# DB25-relay-HV-control.net
KiCad netlist of a schematic drawn in Altium Designer
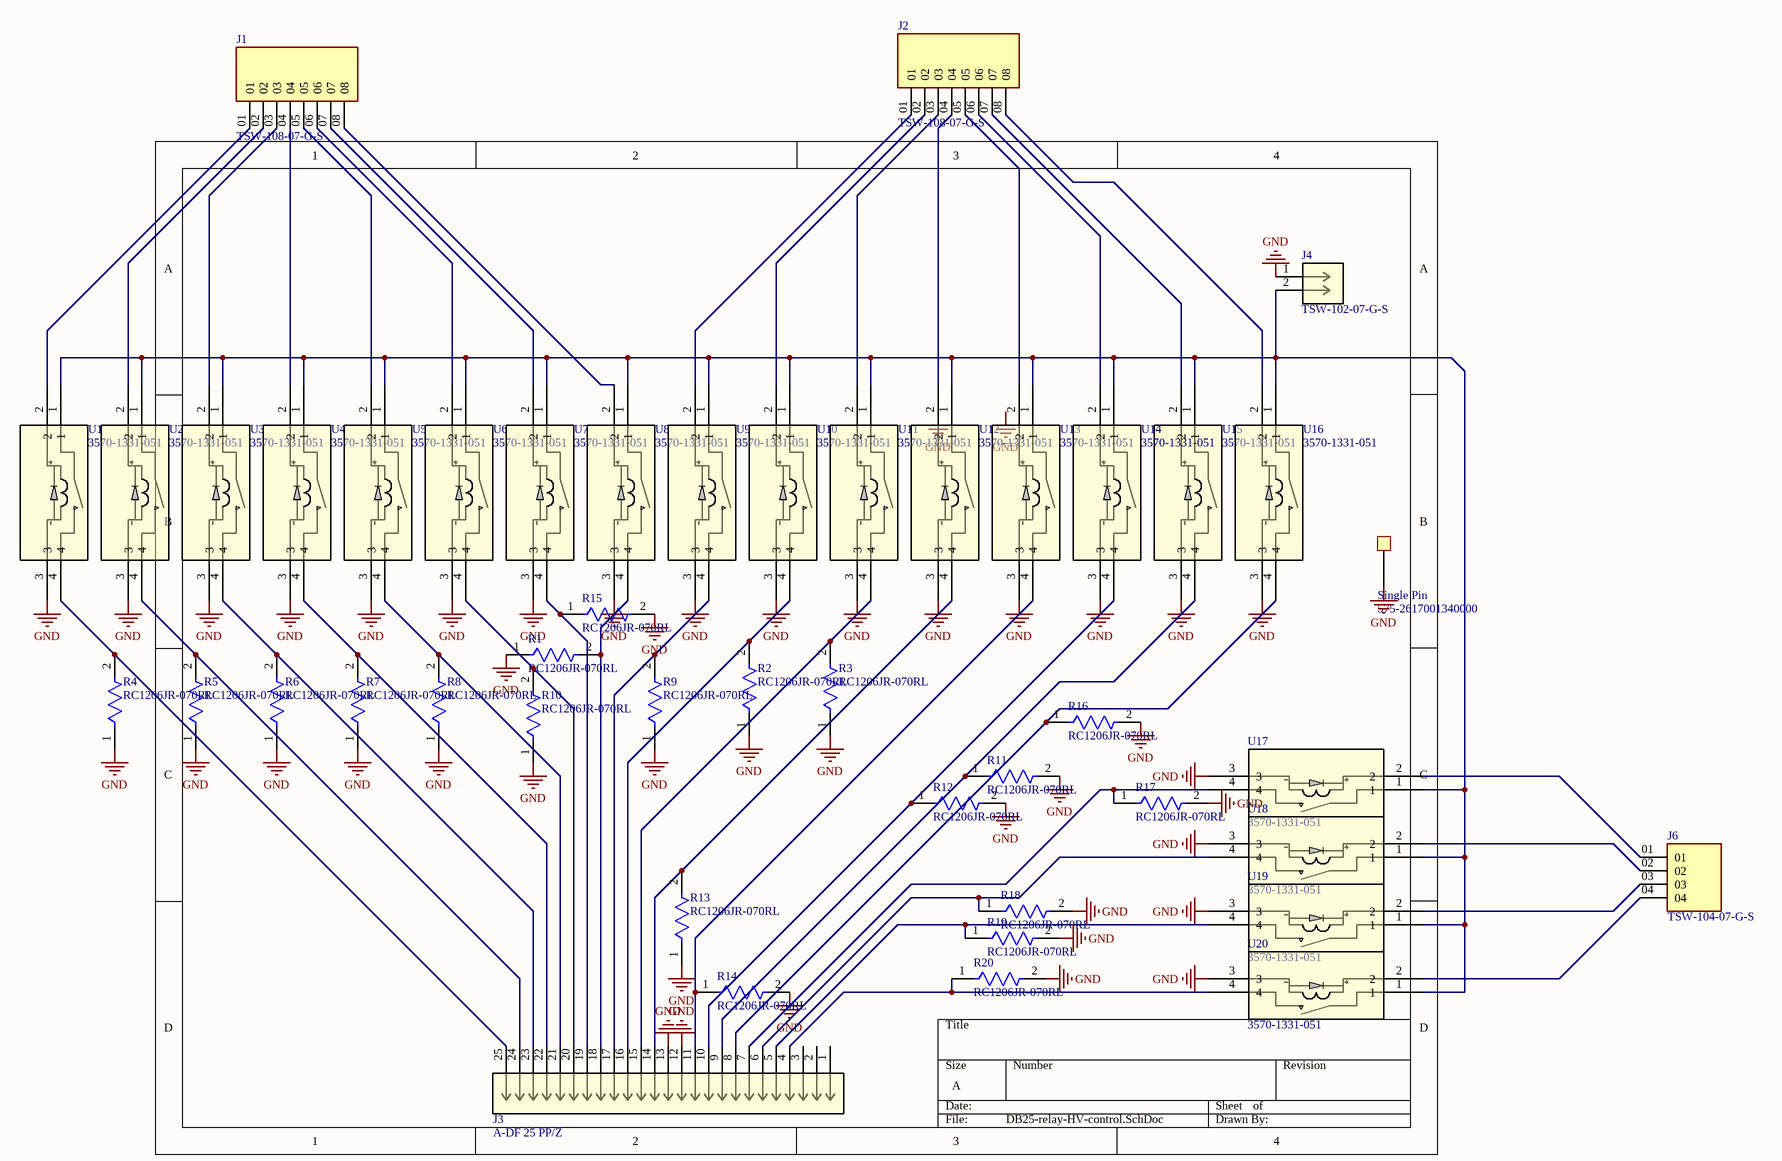
[diagram p0: DB25-relay-HV-control.SchDoc]

(export (version "E")
  (design (tool "Eeschema 10.0.6"))
  (components
    (comp (ref "J1")
      (value "TSW-108-07-G-S")
      (footprint "SAMTEC_TSW-108-07-G-S")
      (description "TSW - Samtec 2.54mm Pin Header 10.92mm Overall Pin Length (07) - Fast Stock")
      (fields (field (name "MF") "Samtec Inc."))
      (libsource (lib "SchlibLafe") (part "TSW-108-07-G-S"))
    )
    (comp (ref "J2")
      (value "TSW-108-07-G-S")
      (footprint "SAMTEC_TSW-108-07-G-S")
      (description "TSW - Samtec 2.54mm Pin Header 10.92mm Overall Pin Length (07) - Fast Stock")
      (fields (field (name "MF") "Samtec Inc."))
      (libsource (lib "SchlibLafe") (part "TSW-108-07-G-S"))
    )
    (comp (ref "J3")
      (value "A-DF 25 PP/Z")
      (footprint "CONN_A-DF 25 PPZ_ASM")
      (description "No Description Available")
      (fields (field (name "COPYRIGHT") "Copyright (C) 2024 Ultra Librarian. All rights reserved."))
      (libsource (lib "SchlibLafe") (part "A-DF 25 PPZ"))
    )
    (comp (ref "J4")
      (value "TSW-102-07-G-S")
      (footprint "CON2_1X2_TU_TSW")
      (description "No Description Available")
      (fields (field (name "COPYRIGHT") "Copyright (C) 2024 Ultra Librarian. All rights reserved."))
      (libsource (lib "SchlibLafe") (part "TSW-102-07-G-S"))
    )
    (comp (ref "J5")
      (value "Single Pin")
      (footprint "Single PC Pin")
      (fields (field (name "SUPPLIER PART NUMBER 1") "575-2617001340000"))
      (libsource (lib "SchlibLafe") (part "Single PC Pin"))
    )
    (comp (ref "J6")
      (value "TSW-104-07-G-S")
      (footprint "SAMTEC_TSW-104-07-G-S")
      (fields (field (name "MP") "altium_native_batch"))
      (libsource (lib "SchlibLafe") (part "TSW-104-07-G-S"))
    )
    (comp (ref "R1")
      (value "RC1206JR-070RL")
      (footprint "FP-RC1206-MFG")
      (description "RES SMD 0 OHM JUMPER 1/4W 1206")
      (fields
        (field (name "MANUFACTURER") "YAGEO")
        (field (name "OCTOPART") "https://octopart.com/rc1206jr-070rl-yageo-40025601")
      )
      (libsource (lib "Altium Content Vault") (part "1029c3af85768c4190bb7ad29bc67b5"))
    )
    (comp (ref "R2")
      (value "RC1206JR-070RL")
      (footprint "FP-RC1206-MFG")
      (description "RES SMD 0 OHM JUMPER 1/4W 1206")
      (fields
        (field (name "MANUFACTURER") "YAGEO")
        (field (name "OCTOPART") "https://octopart.com/rc1206jr-070rl-yageo-40025601")
      )
      (libsource (lib "Altium Content Vault") (part "1029c3af85768c4190bb7ad29bc67b5"))
    )
    (comp (ref "R3")
      (value "RC1206JR-070RL")
      (footprint "FP-RC1206-MFG")
      (description "RES SMD 0 OHM JUMPER 1/4W 1206")
      (fields
        (field (name "MANUFACTURER") "YAGEO")
        (field (name "OCTOPART") "https://octopart.com/rc1206jr-070rl-yageo-40025601")
      )
      (libsource (lib "Altium Content Vault") (part "1029c3af85768c4190bb7ad29bc67b5"))
    )
    (comp (ref "R4")
      (value "RC1206JR-070RL")
      (footprint "FP-RC1206-MFG")
      (description "RES SMD 0 OHM JUMPER 1/4W 1206")
      (fields
        (field (name "MANUFACTURER") "YAGEO")
        (field (name "OCTOPART") "https://octopart.com/rc1206jr-070rl-yageo-40025601")
      )
      (libsource (lib "Altium Content Vault") (part "1029c3af85768c4190bb7ad29bc67b5"))
    )
    (comp (ref "R5")
      (value "RC1206JR-070RL")
      (footprint "FP-RC1206-MFG")
      (description "RES SMD 0 OHM JUMPER 1/4W 1206")
      (fields
        (field (name "MANUFACTURER") "YAGEO")
        (field (name "OCTOPART") "https://octopart.com/rc1206jr-070rl-yageo-40025601")
      )
      (libsource (lib "Altium Content Vault") (part "1029c3af85768c4190bb7ad29bc67b5"))
    )
    (comp (ref "R6")
      (value "RC1206JR-070RL")
      (footprint "FP-RC1206-MFG")
      (description "RES SMD 0 OHM JUMPER 1/4W 1206")
      (fields
        (field (name "MANUFACTURER") "YAGEO")
        (field (name "OCTOPART") "https://octopart.com/rc1206jr-070rl-yageo-40025601")
      )
      (libsource (lib "Altium Content Vault") (part "1029c3af85768c4190bb7ad29bc67b5"))
    )
    (comp (ref "R7")
      (value "RC1206JR-070RL")
      (footprint "FP-RC1206-MFG")
      (description "RES SMD 0 OHM JUMPER 1/4W 1206")
      (fields
        (field (name "MANUFACTURER") "YAGEO")
        (field (name "OCTOPART") "https://octopart.com/rc1206jr-070rl-yageo-40025601")
      )
      (libsource (lib "Altium Content Vault") (part "1029c3af85768c4190bb7ad29bc67b5"))
    )
    (comp (ref "R8")
      (value "RC1206JR-070RL")
      (footprint "FP-RC1206-MFG")
      (description "RES SMD 0 OHM JUMPER 1/4W 1206")
      (fields
        (field (name "MANUFACTURER") "YAGEO")
        (field (name "OCTOPART") "https://octopart.com/rc1206jr-070rl-yageo-40025601")
      )
      (libsource (lib "Altium Content Vault") (part "1029c3af85768c4190bb7ad29bc67b5"))
    )
    (comp (ref "R9")
      (value "RC1206JR-070RL")
      (footprint "FP-RC1206-MFG")
      (description "RES SMD 0 OHM JUMPER 1/4W 1206")
      (fields
        (field (name "MANUFACTURER") "YAGEO")
        (field (name "OCTOPART") "https://octopart.com/rc1206jr-070rl-yageo-40025601")
      )
      (libsource (lib "Altium Content Vault") (part "1029c3af85768c4190bb7ad29bc67b5"))
    )
    (comp (ref "R10")
      (value "RC1206JR-070RL")
      (footprint "FP-RC1206-MFG")
      (description "RES SMD 0 OHM JUMPER 1/4W 1206")
      (fields
        (field (name "MANUFACTURER") "YAGEO")
        (field (name "OCTOPART") "https://octopart.com/rc1206jr-070rl-yageo-40025601")
      )
      (libsource (lib "Altium Content Vault") (part "1029c3af85768c4190bb7ad29bc67b5"))
    )
    (comp (ref "R11")
      (value "RC1206JR-070RL")
      (footprint "FP-RC1206-MFG")
      (description "RES SMD 0 OHM JUMPER 1/4W 1206")
      (fields
        (field (name "MANUFACTURER") "YAGEO")
        (field (name "OCTOPART") "https://octopart.com/rc1206jr-070rl-yageo-40025601")
      )
      (libsource (lib "Altium Content Vault") (part "1029c3af85768c4190bb7ad29bc67b5"))
    )
    (comp (ref "R12")
      (value "RC1206JR-070RL")
      (footprint "FP-RC1206-MFG")
      (description "RES SMD 0 OHM JUMPER 1/4W 1206")
      (fields
        (field (name "MANUFACTURER") "YAGEO")
        (field (name "OCTOPART") "https://octopart.com/rc1206jr-070rl-yageo-40025601")
      )
      (libsource (lib "Altium Content Vault") (part "1029c3af85768c4190bb7ad29bc67b5"))
    )
    (comp (ref "R13")
      (value "RC1206JR-070RL")
      (footprint "FP-RC1206-MFG")
      (description "RES SMD 0 OHM JUMPER 1/4W 1206")
      (fields
        (field (name "MANUFACTURER") "YAGEO")
        (field (name "OCTOPART") "https://octopart.com/rc1206jr-070rl-yageo-40025601")
      )
      (libsource (lib "Altium Content Vault") (part "1029c3af85768c4190bb7ad29bc67b5"))
    )
    (comp (ref "R14")
      (value "RC1206JR-070RL")
      (footprint "FP-RC1206-MFG")
      (description "RES SMD 0 OHM JUMPER 1/4W 1206")
      (fields
        (field (name "MANUFACTURER") "YAGEO")
        (field (name "OCTOPART") "https://octopart.com/rc1206jr-070rl-yageo-40025601")
      )
      (libsource (lib "Altium Content Vault") (part "1029c3af85768c4190bb7ad29bc67b5"))
    )
    (comp (ref "R15")
      (value "RC1206JR-070RL")
      (footprint "FP-RC1206-MFG")
      (description "RES SMD 0 OHM JUMPER 1/4W 1206")
      (fields
        (field (name "MANUFACTURER") "YAGEO")
        (field (name "OCTOPART") "https://octopart.com/rc1206jr-070rl-yageo-40025601")
      )
      (libsource (lib "Altium Content Vault") (part "1029c3af85768c4190bb7ad29bc67b5"))
    )
    (comp (ref "R16")
      (value "RC1206JR-070RL")
      (footprint "FP-RC1206-MFG")
      (description "RES SMD 0 OHM JUMPER 1/4W 1206")
      (fields
        (field (name "MANUFACTURER") "YAGEO")
        (field (name "OCTOPART") "https://octopart.com/rc1206jr-070rl-yageo-40025601")
      )
      (libsource (lib "Altium Content Vault") (part "1029c3af85768c4190bb7ad29bc67b5"))
    )
    (comp (ref "R17")
      (value "RC1206JR-070RL")
      (footprint "FP-RC1206-MFG")
      (description "RES SMD 0 OHM JUMPER 1/4W 1206")
      (fields
        (field (name "MANUFACTURER") "YAGEO")
        (field (name "OCTOPART") "https://octopart.com/rc1206jr-070rl-yageo-40025601")
      )
      (libsource (lib "Altium Content Vault") (part "1029c3af85768c4190bb7ad29bc67b5"))
    )
    (comp (ref "R18")
      (value "RC1206JR-070RL")
      (footprint "FP-RC1206-MFG")
      (description "RES SMD 0 OHM JUMPER 1/4W 1206")
      (fields
        (field (name "MANUFACTURER") "YAGEO")
        (field (name "OCTOPART") "https://octopart.com/rc1206jr-070rl-yageo-40025601")
      )
      (libsource (lib "Altium Content Vault") (part "1029c3af85768c4190bb7ad29bc67b5"))
    )
    (comp (ref "R19")
      (value "RC1206JR-070RL")
      (footprint "FP-RC1206-MFG")
      (description "RES SMD 0 OHM JUMPER 1/4W 1206")
      (fields
        (field (name "MANUFACTURER") "YAGEO")
        (field (name "OCTOPART") "https://octopart.com/rc1206jr-070rl-yageo-40025601")
      )
      (libsource (lib "Altium Content Vault") (part "1029c3af85768c4190bb7ad29bc67b5"))
    )
    (comp (ref "R20")
      (value "RC1206JR-070RL")
      (footprint "FP-RC1206-MFG")
      (description "RES SMD 0 OHM JUMPER 1/4W 1206")
      (fields
        (field (name "MANUFACTURER") "YAGEO")
        (field (name "OCTOPART") "https://octopart.com/rc1206jr-070rl-yageo-40025601")
      )
      (libsource (lib "Altium Content Vault") (part "1029c3af85768c4190bb7ad29bc67b5"))
    )
    (comp (ref "U1")
      (value "3570-1331-051")
      (footprint "SIP_3570-1331_COM")
      (description "No Description Available")
      (fields (field (name "COPYRIGHT") "Copyright (C) 2024 Ultra Librarian. All rights reserved."))
      (libsource (lib "") (part "3570-1331-051_2"))
    )
    (comp (ref "U2")
      (value "3570-1331-051")
      (footprint "SIP_3570-1331_COM")
      (description "No Description Available")
      (fields (field (name "COPYRIGHT") "Copyright (C) 2024 Ultra Librarian. All rights reserved."))
      (libsource (lib "") (part "3570-1331-051_3"))
    )
    (comp (ref "U3")
      (value "3570-1331-051")
      (footprint "SIP_3570-1331_COM")
      (description "No Description Available")
      (fields (field (name "COPYRIGHT") "Copyright (C) 2024 Ultra Librarian. All rights reserved."))
      (libsource (lib "SchlibAnna") (part "3570-1331-051"))
    )
    (comp (ref "U4")
      (value "3570-1331-051")
      (footprint "SIP_3570-1331_COM")
      (description "No Description Available")
      (fields (field (name "COPYRIGHT") "Copyright (C) 2024 Ultra Librarian. All rights reserved."))
      (libsource (lib "SchlibAnna") (part "3570-1331-051"))
    )
    (comp (ref "U5")
      (value "3570-1331-051")
      (footprint "SIP_3570-1331_COM")
      (description "No Description Available")
      (fields (field (name "COPYRIGHT") "Copyright (C) 2024 Ultra Librarian. All rights reserved."))
      (libsource (lib "SchlibAnna") (part "3570-1331-051"))
    )
    (comp (ref "U6")
      (value "3570-1331-051")
      (footprint "SIP_3570-1331_COM")
      (description "No Description Available")
      (fields (field (name "COPYRIGHT") "Copyright (C) 2024 Ultra Librarian. All rights reserved."))
      (libsource (lib "SchlibAnna") (part "3570-1331-051"))
    )
    (comp (ref "U7")
      (value "3570-1331-051")
      (footprint "SIP_3570-1331_COM")
      (description "No Description Available")
      (fields (field (name "COPYRIGHT") "Copyright (C) 2024 Ultra Librarian. All rights reserved."))
      (libsource (lib "SchlibAnna") (part "3570-1331-051"))
    )
    (comp (ref "U8")
      (value "3570-1331-051")
      (footprint "SIP_3570-1331_COM")
      (description "No Description Available")
      (fields (field (name "COPYRIGHT") "Copyright (C) 2024 Ultra Librarian. All rights reserved."))
      (libsource (lib "SchlibAnna") (part "3570-1331-051"))
    )
    (comp (ref "U9")
      (value "3570-1331-051")
      (footprint "SIP_3570-1331_COM")
      (description "No Description Available")
      (fields (field (name "COPYRIGHT") "Copyright (C) 2024 Ultra Librarian. All rights reserved."))
      (libsource (lib "SchlibAnna") (part "3570-1331-051"))
    )
    (comp (ref "U10")
      (value "3570-1331-051")
      (footprint "SIP_3570-1331_COM")
      (description "No Description Available")
      (fields (field (name "COPYRIGHT") "Copyright (C) 2024 Ultra Librarian. All rights reserved."))
      (libsource (lib "SchlibAnna") (part "3570-1331-051"))
    )
    (comp (ref "U11")
      (value "3570-1331-051")
      (footprint "SIP_3570-1331_COM")
      (description "No Description Available")
      (fields (field (name "COPYRIGHT") "Copyright (C) 2024 Ultra Librarian. All rights reserved."))
      (libsource (lib "SchlibAnna") (part "3570-1331-051"))
    )
    (comp (ref "U12")
      (value "3570-1331-051")
      (footprint "SIP_3570-1331_COM")
      (description "No Description Available")
      (fields (field (name "COPYRIGHT") "Copyright (C) 2024 Ultra Librarian. All rights reserved."))
      (libsource (lib "SchlibAnna") (part "3570-1331-051"))
    )
    (comp (ref "U13")
      (value "3570-1331-051")
      (footprint "SIP_3570-1331_COM")
      (description "No Description Available")
      (fields (field (name "COPYRIGHT") "Copyright (C) 2024 Ultra Librarian. All rights reserved."))
      (libsource (lib "SchlibAnna") (part "3570-1331-051"))
    )
    (comp (ref "U14")
      (value "3570-1331-051")
      (footprint "SIP_3570-1331_COM")
      (description "No Description Available")
      (fields (field (name "COPYRIGHT") "Copyright (C) 2024 Ultra Librarian. All rights reserved."))
      (libsource (lib "SchlibAnna") (part "3570-1331-051"))
    )
    (comp (ref "U15")
      (value "3570-1331-051")
      (footprint "SIP_3570-1331_COM")
      (description "No Description Available")
      (fields (field (name "COPYRIGHT") "Copyright (C) 2024 Ultra Librarian. All rights reserved."))
      (libsource (lib "SchlibAnna") (part "3570-1331-051"))
    )
    (comp (ref "U16")
      (value "3570-1331-051")
      (footprint "SIP_3570-1331_COM")
      (description "No Description Available")
      (fields (field (name "COPYRIGHT") "Copyright (C) 2024 Ultra Librarian. All rights reserved."))
      (libsource (lib "SchlibAnna") (part "3570-1331-051"))
    )
    (comp (ref "U17")
      (value "3570-1331-051")
      (footprint "SIP_3570-1331_COM")
      (description "No Description Available")
      (fields (field (name "COPYRIGHT") "Copyright (C) 2024 Ultra Librarian. All rights reserved."))
      (libsource (lib "") (part "3570-1331-051_1"))
    )
    (comp (ref "U18")
      (value "3570-1331-051")
      (footprint "SIP_3570-1331_COM")
      (description "No Description Available")
      (fields (field (name "COPYRIGHT") "Copyright (C) 2024 Ultra Librarian. All rights reserved."))
      (libsource (lib "") (part "3570-1331-051_1"))
    )
    (comp (ref "U19")
      (value "3570-1331-051")
      (footprint "SIP_3570-1331_COM")
      (description "No Description Available")
      (fields (field (name "COPYRIGHT") "Copyright (C) 2024 Ultra Librarian. All rights reserved."))
      (libsource (lib "") (part "3570-1331-051_1"))
    )
    (comp (ref "U20")
      (value "3570-1331-051")
      (footprint "SIP_3570-1331_COM")
      (description "No Description Available")
      (fields (field (name "COPYRIGHT") "Copyright (C) 2024 Ultra Librarian. All rights reserved."))
      (libsource (lib "") (part "3570-1331-051_1"))
    )
  )
  (nets
    (net (code "1") (name "GND") (class "Default")
      (node (ref "J3") (pin "12") (pinfunction "12_12") (pintype "passive"))
      (node (ref "J3") (pin "13") (pinfunction "13_13") (pintype "passive"))
      (node (ref "J4") (pin "1") (pinfunction "1_1") (pintype "passive"))
      (node (ref "J5") (pin "1") (pinfunction "1_1") (pintype "passive"))
      (node (ref "R1") (pin "1") (pinfunction "1_1") (pintype "passive"))
      (node (ref "R10") (pin "1") (pinfunction "1_1") (pintype "passive"))
      (node (ref "R11") (pin "2") (pinfunction "2_2") (pintype "passive"))
      (node (ref "R12") (pin "2") (pinfunction "2_2") (pintype "passive"))
      (node (ref "R13") (pin "1") (pinfunction "1_1") (pintype "passive"))
      (node (ref "R14") (pin "2") (pinfunction "2_2") (pintype "passive"))
      (node (ref "R15") (pin "2") (pinfunction "2_2") (pintype "passive"))
      (node (ref "R16") (pin "2") (pinfunction "2_2") (pintype "passive"))
      (node (ref "R17") (pin "2") (pinfunction "2_2") (pintype "passive"))
      (node (ref "R18") (pin "2") (pinfunction "2_2") (pintype "passive"))
      (node (ref "R19") (pin "2") (pinfunction "2_2") (pintype "passive"))
      (node (ref "R2") (pin "1") (pinfunction "1_1") (pintype "passive"))
      (node (ref "R20") (pin "2") (pinfunction "2_2") (pintype "passive"))
      (node (ref "R3") (pin "1") (pinfunction "1_1") (pintype "passive"))
      (node (ref "R4") (pin "1") (pinfunction "1_1") (pintype "passive"))
      (node (ref "R5") (pin "1") (pinfunction "1_1") (pintype "passive"))
      (node (ref "R6") (pin "1") (pinfunction "1_1") (pintype "passive"))
      (node (ref "R7") (pin "1") (pinfunction "1_1") (pintype "passive"))
      (node (ref "R8") (pin "1") (pinfunction "1_1") (pintype "passive"))
      (node (ref "R9") (pin "1") (pinfunction "1_1") (pintype "passive"))
      (node (ref "U1") (pin "3") (pinfunction "3_3") (pintype "passive"))
      (node (ref "U10") (pin "3") (pinfunction "3_3") (pintype "passive"))
      (node (ref "U11") (pin "3") (pinfunction "3_3") (pintype "passive"))
      (node (ref "U12") (pin "3") (pinfunction "3_3") (pintype "passive"))
      (node (ref "U13") (pin "3") (pinfunction "3_3") (pintype "passive"))
      (node (ref "U14") (pin "3") (pinfunction "3_3") (pintype "passive"))
      (node (ref "U15") (pin "3") (pinfunction "3_3") (pintype "passive"))
      (node (ref "U16") (pin "3") (pinfunction "3_3") (pintype "passive"))
      (node (ref "U17") (pin "3") (pinfunction "3_3") (pintype "passive"))
      (node (ref "U18") (pin "3") (pinfunction "3_3") (pintype "passive"))
      (node (ref "U19") (pin "3") (pinfunction "3_3") (pintype "passive"))
      (node (ref "U2") (pin "3") (pinfunction "3_3") (pintype "passive"))
      (node (ref "U20") (pin "3") (pinfunction "3_3") (pintype "passive"))
      (node (ref "U3") (pin "3") (pinfunction "3_3") (pintype "passive"))
      (node (ref "U4") (pin "3") (pinfunction "3_3") (pintype "passive"))
      (node (ref "U5") (pin "3") (pinfunction "3_3") (pintype "passive"))
      (node (ref "U6") (pin "3") (pinfunction "3_3") (pintype "passive"))
      (node (ref "U7") (pin "3") (pinfunction "3_3") (pintype "passive"))
      (node (ref "U8") (pin "3") (pinfunction "3_3") (pintype "passive"))
      (node (ref "U9") (pin "3") (pinfunction "3_3") (pintype "passive"))
    )
    (net (code "2") (name "Net-(J1-Pad01)") (class "Default")
      (node (ref "J1") (pin "01") (pinfunction "01_01") (pintype "passive"))
      (node (ref "U1") (pin "2") (pinfunction "2_2") (pintype "passive"))
    )
    (net (code "3") (name "Net-(J1-Pad02)") (class "Default")
      (node (ref "J1") (pin "02") (pinfunction "02_02") (pintype "passive"))
      (node (ref "U2") (pin "2") (pinfunction "2_2") (pintype "passive"))
    )
    (net (code "4") (name "Net-(J1-Pad03)") (class "Default")
      (node (ref "J1") (pin "03") (pinfunction "03_03") (pintype "passive"))
      (node (ref "U3") (pin "2") (pinfunction "2_2") (pintype "passive"))
    )
    (net (code "5") (name "Net-(J1-Pad04)") (class "Default")
      (node (ref "J1") (pin "04") (pinfunction "04_04") (pintype "passive"))
      (node (ref "U4") (pin "2") (pinfunction "2_2") (pintype "passive"))
    )
    (net (code "6") (name "Net-(J1-Pad05)") (class "Default")
      (node (ref "J1") (pin "05") (pinfunction "05_05") (pintype "passive"))
      (node (ref "U5") (pin "2") (pinfunction "2_2") (pintype "passive"))
    )
    (net (code "7") (name "Net-(J1-Pad06)") (class "Default")
      (node (ref "J1") (pin "06") (pinfunction "06_06") (pintype "passive"))
      (node (ref "U6") (pin "2") (pinfunction "2_2") (pintype "passive"))
    )
    (net (code "8") (name "Net-(J1-Pad07)") (class "Default")
      (node (ref "J1") (pin "07") (pinfunction "07_07") (pintype "passive"))
      (node (ref "U7") (pin "2") (pinfunction "2_2") (pintype "passive"))
    )
    (net (code "9") (name "Net-(J1-Pad08)") (class "Default")
      (node (ref "J1") (pin "08") (pinfunction "08_08") (pintype "passive"))
      (node (ref "U8") (pin "2") (pinfunction "2_2") (pintype "passive"))
    )
    (net (code "10") (name "Net-(J2-Pad01)") (class "Default")
      (node (ref "J2") (pin "01") (pinfunction "01_01") (pintype "passive"))
      (node (ref "U9") (pin "2") (pinfunction "2_2") (pintype "passive"))
    )
    (net (code "11") (name "Net-(J2-Pad02)") (class "Default")
      (node (ref "J2") (pin "02") (pinfunction "02_02") (pintype "passive"))
      (node (ref "U10") (pin "2") (pinfunction "2_2") (pintype "passive"))
    )
    (net (code "12") (name "Net-(J2-Pad03)") (class "Default")
      (node (ref "J2") (pin "03") (pinfunction "03_03") (pintype "passive"))
      (node (ref "U11") (pin "2") (pinfunction "2_2") (pintype "passive"))
    )
    (net (code "13") (name "Net-(J2-Pad04)") (class "Default")
      (node (ref "J2") (pin "04") (pinfunction "04_04") (pintype "passive"))
      (node (ref "U12") (pin "2") (pinfunction "2_2") (pintype "passive"))
    )
    (net (code "14") (name "Net-(J2-Pad05)") (class "Default")
      (node (ref "J2") (pin "05") (pinfunction "05_05") (pintype "passive"))
      (node (ref "U13") (pin "2") (pinfunction "2_2") (pintype "passive"))
    )
    (net (code "15") (name "Net-(J2-Pad06)") (class "Default")
      (node (ref "J2") (pin "06") (pinfunction "06_06") (pintype "passive"))
      (node (ref "U14") (pin "2") (pinfunction "2_2") (pintype "passive"))
    )
    (net (code "16") (name "Net-(J2-Pad07)") (class "Default")
      (node (ref "J2") (pin "07") (pinfunction "07_07") (pintype "passive"))
      (node (ref "U15") (pin "2") (pinfunction "2_2") (pintype "passive"))
    )
    (net (code "17") (name "Net-(J2-Pad08)") (class "Default")
      (node (ref "J2") (pin "08") (pinfunction "08_08") (pintype "passive"))
      (node (ref "U16") (pin "2") (pinfunction "2_2") (pintype "passive"))
    )
    (net (code "18") (name "Net-(J3-Pad4)") (class "Default")
      (node (ref "J3") (pin "4") (pinfunction "4_4") (pintype "passive"))
      (node (ref "R20") (pin "1") (pinfunction "1_1") (pintype "passive"))
      (node (ref "U20") (pin "4") (pinfunction "4_4") (pintype "passive"))
    )
    (net (code "19") (name "Net-(J3-Pad5)") (class "Default")
      (node (ref "J3") (pin "5") (pinfunction "5_5") (pintype "passive"))
      (node (ref "R19") (pin "1") (pinfunction "1_1") (pintype "passive"))
      (node (ref "U19") (pin "4") (pinfunction "4_4") (pintype "passive"))
    )
    (net (code "20") (name "Net-(J3-Pad6)") (class "Default")
      (node (ref "J3") (pin "6") (pinfunction "6_6") (pintype "passive"))
      (node (ref "R18") (pin "1") (pinfunction "1_1") (pintype "passive"))
      (node (ref "U18") (pin "4") (pinfunction "4_4") (pintype "passive"))
    )
    (net (code "21") (name "Net-(J3-Pad7)") (class "Default")
      (node (ref "J3") (pin "7") (pinfunction "7_7") (pintype "passive"))
      (node (ref "R17") (pin "1") (pinfunction "1_1") (pintype "passive"))
      (node (ref "U17") (pin "4") (pinfunction "4_4") (pintype "passive"))
    )
    (net (code "22") (name "Net-(J3-Pad8)") (class "Default")
      (node (ref "J3") (pin "8") (pinfunction "8_8") (pintype "passive"))
      (node (ref "R16") (pin "1") (pinfunction "1_1") (pintype "passive"))
      (node (ref "U16") (pin "4") (pinfunction "4_4") (pintype "passive"))
    )
    (net (code "23") (name "Net-(J3-Pad9)") (class "Default")
      (node (ref "J3") (pin "9") (pinfunction "9_9") (pintype "passive"))
      (node (ref "R11") (pin "1") (pinfunction "1_1") (pintype "passive"))
      (node (ref "U15") (pin "4") (pinfunction "4_4") (pintype "passive"))
    )
    (net (code "24") (name "Net-(J3-Pad10)") (class "Default")
      (node (ref "J3") (pin "10") (pinfunction "10_10") (pintype "passive"))
      (node (ref "R12") (pin "1") (pinfunction "1_1") (pintype "passive"))
      (node (ref "U14") (pin "4") (pinfunction "4_4") (pintype "passive"))
    )
    (net (code "25") (name "Net-(J3-Pad11)") (class "Default")
      (node (ref "J3") (pin "11") (pinfunction "11_11") (pintype "passive"))
      (node (ref "R14") (pin "1") (pinfunction "1_1") (pintype "passive"))
      (node (ref "U13") (pin "4") (pinfunction "4_4") (pintype "passive"))
    )
    (net (code "26") (name "Net-(J3-Pad14)") (class "Default")
      (node (ref "J3") (pin "14") (pinfunction "14_14") (pintype "passive"))
      (node (ref "R13") (pin "2") (pinfunction "2_2") (pintype "passive"))
      (node (ref "U12") (pin "4") (pinfunction "4_4") (pintype "passive"))
    )
    (net (code "27") (name "Net-(J3-Pad15)") (class "Default")
      (node (ref "J3") (pin "15") (pinfunction "15_15") (pintype "passive"))
      (node (ref "R3") (pin "2") (pinfunction "2_2") (pintype "passive"))
      (node (ref "U11") (pin "4") (pinfunction "4_4") (pintype "passive"))
    )
    (net (code "28") (name "Net-(J3-Pad16)") (class "Default")
      (node (ref "J3") (pin "16") (pinfunction "16_16") (pintype "passive"))
      (node (ref "R2") (pin "2") (pinfunction "2_2") (pintype "passive"))
      (node (ref "U10") (pin "4") (pinfunction "4_4") (pintype "passive"))
    )
    (net (code "29") (name "Net-(J3-Pad17)") (class "Default")
      (node (ref "J3") (pin "17") (pinfunction "17_17") (pintype "passive"))
      (node (ref "R9") (pin "2") (pinfunction "2_2") (pintype "passive"))
      (node (ref "U9") (pin "4") (pinfunction "4_4") (pintype "passive"))
    )
    (net (code "30") (name "Net-(J3-Pad18)") (class "Default")
      (node (ref "J3") (pin "18") (pinfunction "18_18") (pintype "passive"))
      (node (ref "R1") (pin "2") (pinfunction "2_2") (pintype "passive"))
      (node (ref "U8") (pin "4") (pinfunction "4_4") (pintype "passive"))
    )
    (net (code "31") (name "Net-(J3-Pad19)") (class "Default")
      (node (ref "J3") (pin "19") (pinfunction "19_19") (pintype "passive"))
      (node (ref "R15") (pin "1") (pinfunction "1_1") (pintype "passive"))
      (node (ref "U7") (pin "4") (pinfunction "4_4") (pintype "passive"))
    )
    (net (code "32") (name "Net-(J3-Pad20)") (class "Default")
      (node (ref "J3") (pin "20") (pinfunction "20_20") (pintype "passive"))
      (node (ref "R10") (pin "2") (pinfunction "2_2") (pintype "passive"))
      (node (ref "U6") (pin "4") (pinfunction "4_4") (pintype "passive"))
    )
    (net (code "33") (name "Net-(J3-Pad21)") (class "Default")
      (node (ref "J3") (pin "21") (pinfunction "21_21") (pintype "passive"))
      (node (ref "R8") (pin "2") (pinfunction "2_2") (pintype "passive"))
      (node (ref "U5") (pin "4") (pinfunction "4_4") (pintype "passive"))
    )
    (net (code "34") (name "Net-(J3-Pad22)") (class "Default")
      (node (ref "J3") (pin "22") (pinfunction "22_22") (pintype "passive"))
      (node (ref "R7") (pin "2") (pinfunction "2_2") (pintype "passive"))
      (node (ref "U4") (pin "4") (pinfunction "4_4") (pintype "passive"))
    )
    (net (code "35") (name "Net-(J3-Pad23)") (class "Default")
      (node (ref "J3") (pin "23") (pinfunction "23_23") (pintype "passive"))
      (node (ref "R6") (pin "2") (pinfunction "2_2") (pintype "passive"))
      (node (ref "U3") (pin "4") (pinfunction "4_4") (pintype "passive"))
    )
    (net (code "36") (name "Net-(J3-Pad24)") (class "Default")
      (node (ref "J3") (pin "24") (pinfunction "24_24") (pintype "passive"))
      (node (ref "R5") (pin "2") (pinfunction "2_2") (pintype "passive"))
      (node (ref "U2") (pin "4") (pinfunction "4_4") (pintype "passive"))
    )
    (net (code "37") (name "Net-(J3-Pad25)") (class "Default")
      (node (ref "J3") (pin "25") (pinfunction "25_25") (pintype "passive"))
      (node (ref "R4") (pin "2") (pinfunction "2_2") (pintype "passive"))
      (node (ref "U1") (pin "4") (pinfunction "4_4") (pintype "passive"))
    )
    (net (code "38") (name "Net-(J4-Pad2)") (class "Default")
      (node (ref "J4") (pin "2") (pinfunction "2_2") (pintype "passive"))
      (node (ref "U1") (pin "1") (pinfunction "1_1") (pintype "passive"))
      (node (ref "U10") (pin "1") (pinfunction "1_1") (pintype "passive"))
      (node (ref "U11") (pin "1") (pinfunction "1_1") (pintype "passive"))
      (node (ref "U12") (pin "1") (pinfunction "1_1") (pintype "passive"))
      (node (ref "U13") (pin "1") (pinfunction "1_1") (pintype "passive"))
      (node (ref "U14") (pin "1") (pinfunction "1_1") (pintype "passive"))
      (node (ref "U15") (pin "1") (pinfunction "1_1") (pintype "passive"))
      (node (ref "U16") (pin "1") (pinfunction "1_1") (pintype "passive"))
      (node (ref "U17") (pin "1") (pinfunction "1_1") (pintype "passive"))
      (node (ref "U18") (pin "1") (pinfunction "1_1") (pintype "passive"))
      (node (ref "U19") (pin "1") (pinfunction "1_1") (pintype "passive"))
      (node (ref "U2") (pin "1") (pinfunction "1_1") (pintype "passive"))
      (node (ref "U20") (pin "1") (pinfunction "1_1") (pintype "passive"))
      (node (ref "U3") (pin "1") (pinfunction "1_1") (pintype "passive"))
      (node (ref "U4") (pin "1") (pinfunction "1_1") (pintype "passive"))
      (node (ref "U5") (pin "1") (pinfunction "1_1") (pintype "passive"))
      (node (ref "U6") (pin "1") (pinfunction "1_1") (pintype "passive"))
      (node (ref "U7") (pin "1") (pinfunction "1_1") (pintype "passive"))
      (node (ref "U8") (pin "1") (pinfunction "1_1") (pintype "passive"))
      (node (ref "U9") (pin "1") (pinfunction "1_1") (pintype "passive"))
    )
    (net (code "39") (name "Net-(J6-Pad01)") (class "Default")
      (node (ref "J6") (pin "01") (pinfunction "01_01") (pintype "passive"))
      (node (ref "U17") (pin "2") (pinfunction "2_2") (pintype "passive"))
    )
    (net (code "40") (name "Net-(J6-Pad02)") (class "Default")
      (node (ref "J6") (pin "02") (pinfunction "02_02") (pintype "passive"))
      (node (ref "U18") (pin "2") (pinfunction "2_2") (pintype "passive"))
    )
    (net (code "41") (name "Net-(J6-Pad03)") (class "Default")
      (node (ref "J6") (pin "03") (pinfunction "03_03") (pintype "passive"))
      (node (ref "U19") (pin "2") (pinfunction "2_2") (pintype "passive"))
    )
    (net (code "42") (name "Net-(J6-Pad04)") (class "Default")
      (node (ref "J6") (pin "04") (pinfunction "04_04") (pintype "passive"))
      (node (ref "U20") (pin "2") (pinfunction "2_2") (pintype "passive"))
    )
    (net (code "43") (name "unconnected-(J3-Pad1)") (class "Default")
      (node (ref "J3") (pin "1") (pinfunction "1_1") (pintype "passive"))
    )
    (net (code "44") (name "unconnected-(J3-Pad2)") (class "Default")
      (node (ref "J3") (pin "2") (pinfunction "2_2") (pintype "passive"))
    )
    (net (code "45") (name "unconnected-(J3-Pad3)") (class "Default")
      (node (ref "J3") (pin "3") (pinfunction "3_3") (pintype "passive"))
    )
  )
)
